# ProPrj_digisparkI2C_module_2026-01-09.net
KiCad netlist of a schematic drawn in EasyEDA Pro
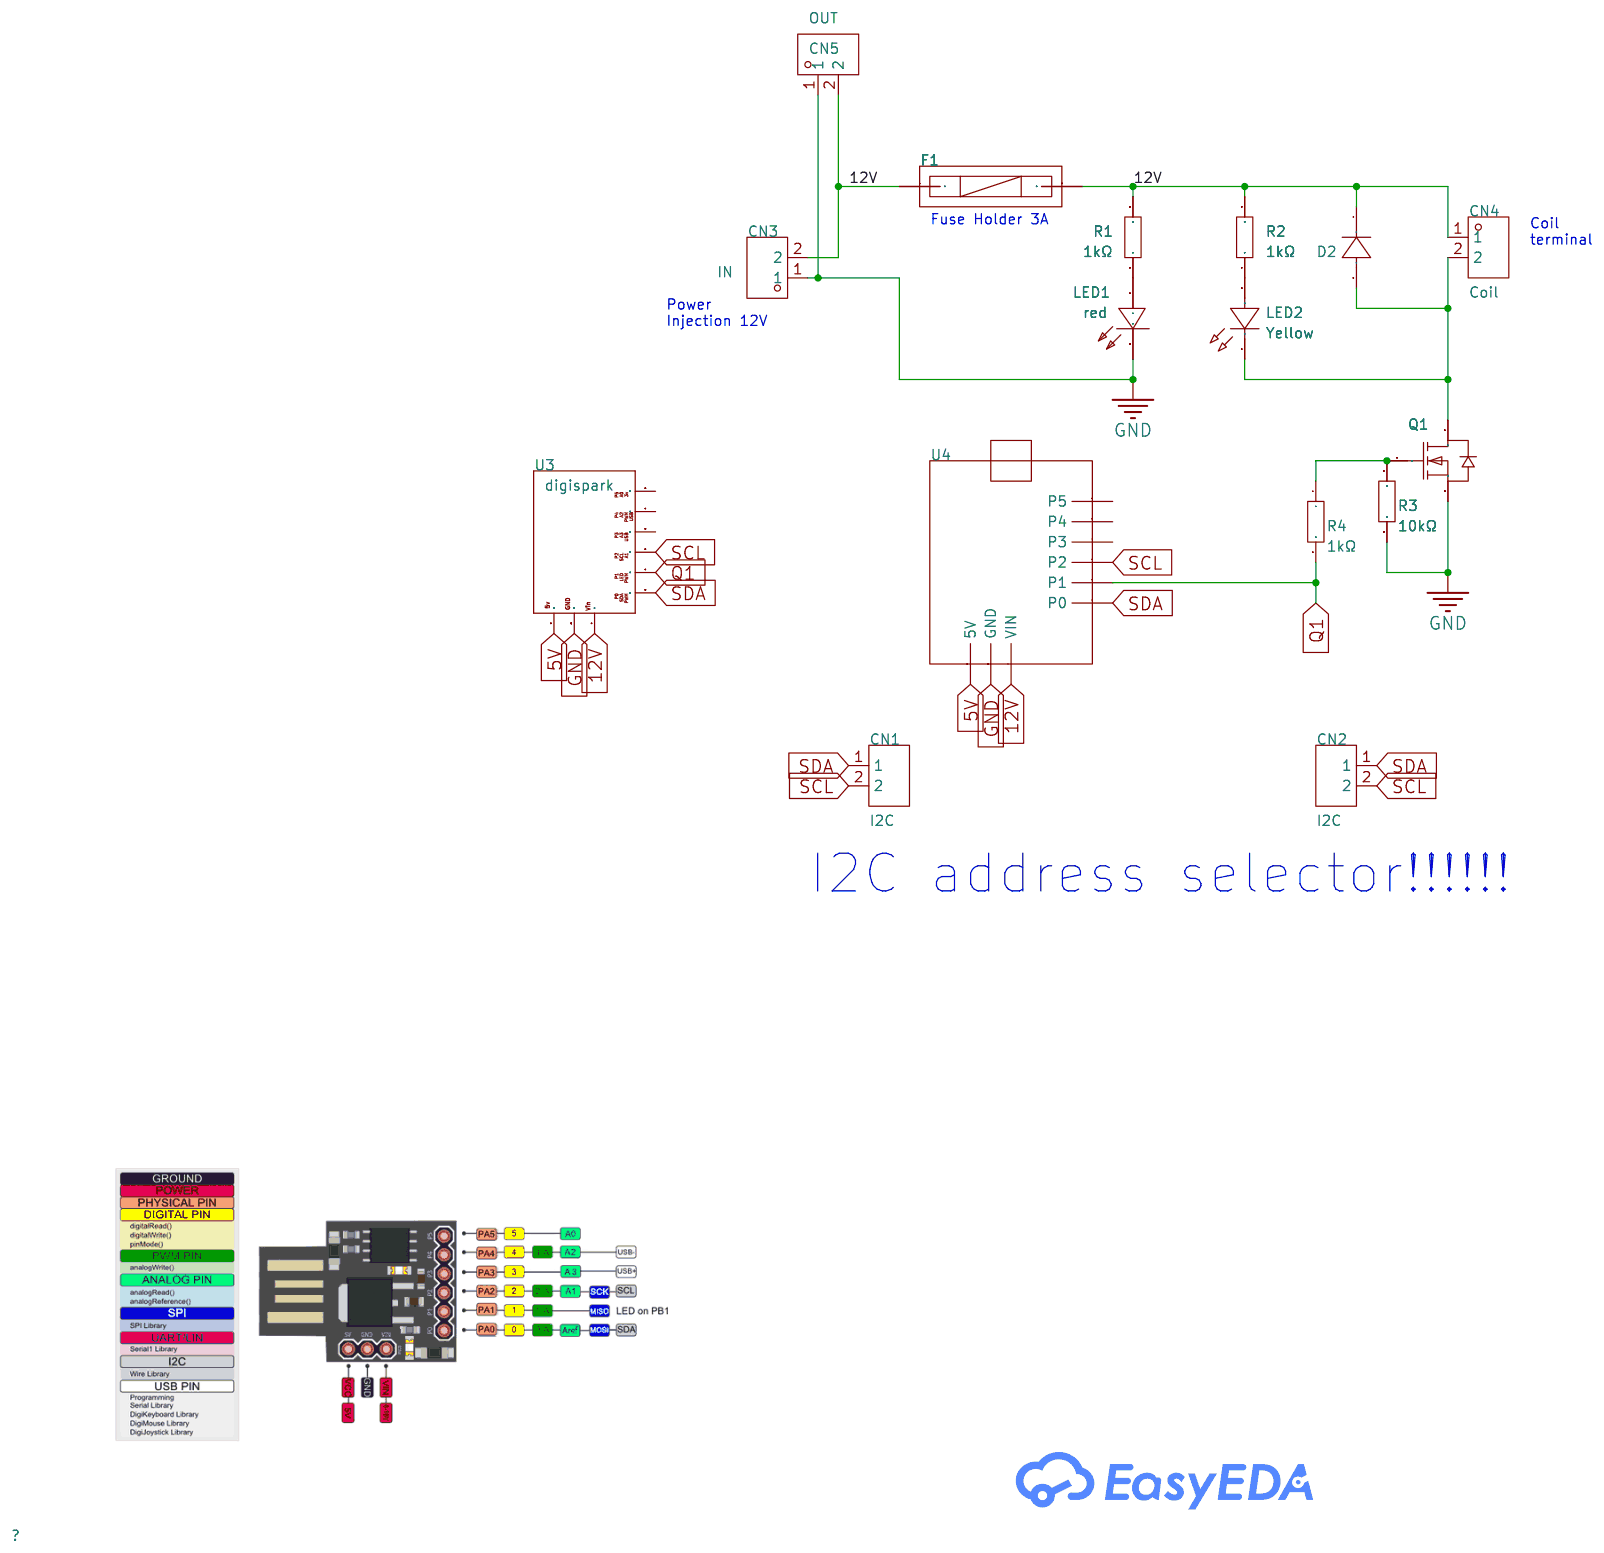
[diagram p0: schematic sheet]

(export (version "E")
  (design (tool "Eeschema 10.0.6"))
  (components
    (comp (ref "CN1")
      (value "I2C")
      (footprint "easyedapro:CONN-TH_2P-P2.50_XY-XH2.54-2A11-YT")
      (fields
        (field (name "Manufacturer Part") "XY-XH2.54-2A11-YT")
        (field (name "Manufacturer") "XYECONN(辛译)")
      )
      (libsource (lib "easyedapro") (part "XY-XH2.54-2A11-YT"))
    )
    (comp (ref "CN2")
      (value "I2C")
      (footprint "easyedapro:CONN-TH_2P-P2.50_XY-XH2.54-2A11-YT")
      (fields
        (field (name "Manufacturer Part") "XY-XH2.54-2A11-YT")
        (field (name "Manufacturer") "XYECONN(辛译)")
      )
      (libsource (lib "easyedapro") (part "XY-XH2.54-2A11-YT"))
    )
    (comp (ref "CN3")
      (value "IN")
      (footprint "easyedapro:CONN-TH_2P-P5.00_MX126-5.0-GN01-02P-CU-S-A")
      (fields
        (field (name "Manufacturer Part") "MX126-5.0-02P-GN01-Cu-S-A")
        (field (name "Manufacturer") "MAX(迈旭)")
      )
      (libsource (lib "easyedapro") (part "MX126-5.0-GN01-02P-CU-S-A"))
    )
    (comp (ref "CN4")
      (value "Coil")
      (footprint "easyedapro:CONN-TH_2P-P5.00_MX126-5.0-GN01-02P-CU-S-A")
      (fields
        (field (name "Manufacturer Part") "MX126-5.0-02P-GN01-Cu-S-A")
        (field (name "Manufacturer") "MAX(迈旭)")
      )
      (libsource (lib "easyedapro") (part "MX126-5.0-GN01-02P-CU-S-A"))
    )
    (comp (ref "CN5")
      (value "OUT")
      (footprint "easyedapro:CONN-TH_2P-P5.00_MX126-5.0-GN01-02P-CU-S-A")
      (fields
        (field (name "Manufacturer Part") "MX126-5.0-02P-GN01-Cu-S-A")
        (field (name "Manufacturer") "MAX(迈旭)")
      )
      (libsource (lib "easyedapro") (part "MX126-5.0-GN01-02P-CU-S-A"))
    )
    (comp (ref "D2")
      (value "~")
      (footprint "easyedapro:SMA_L4.4-W2.8-LS5.4-RD")
      (libsource (lib "easyedapro") (part "D_1N4007"))
    )
    (comp (ref "F1")
      (value "保险丝透明座")
      (footprint "easyedapro:FUSE-TH_L24.5-W9.8-P22.5")
      (description "Fuseholder Type:- Fuse Type:- Fuse Size:-")
      (fields (field (name "Manufacturer") "xcfuse(旭程)"))
      (libsource (lib "easyedapro") (part "Fuse transparent seat"))
    )
    (comp (ref "LED1")
      (value "red")
      (footprint "easyedapro:LED0805-R-RD-1")
      (description "Illumination Color:Red")
      (fields
        (field (name "Manufacturer Part") "17-21SURC/S530-A2/TR8")
        (field (name "Manufacturer") "EVERLIGHT(亿光)")
      )
      (libsource (lib "easyedapro") (part "17-21SURC/S530-A2/TR8"))
    )
    (comp (ref "LED2")
      (value "Yellow")
      (footprint "easyedapro:LED0805-RD_YELLOW")
      (fields (field (name "Manufacturer Part") "YLED0805Y") (field (name "Manufacturer") "YONGYUTAI(永裕泰)"))
      (libsource (lib "easyedapro") (part "YLED0805Y"))
    )
    (comp (ref "Q1")
      (value "IRLZ44NPBF-HXY")
      (footprint "easyedapro:TO-220-3_L9.9-W4.5-P2.54-L-1")
      (fields (field (name "Manufacturer") "HXY MOSFET(华轩阳电子)"))
      (libsource (lib "easyedapro") (part "IRLZ44NPBF-HXY"))
    )
    (comp (ref "R1") (value "1kΩ") (footprint "easyedapro:R1206") (libsource (lib "easyedapro") (part "Res")))
    (comp (ref "R2") (value "1kΩ") (footprint "easyedapro:R1206") (libsource (lib "easyedapro") (part "Res")))
    (comp (ref "R3")
      (value "10kΩ")
      (footprint "easyedapro:R1206")
      (libsource (lib "easyedapro") (part "Res"))
    )
    (comp (ref "R4") (value "1kΩ") (footprint "easyedapro:R1206") (libsource (lib "easyedapro") (part "Res")))
    (comp (ref "U3")
      (value "digispark")
      (footprint "easyedapro:DIGISPARK")
      (libsource (lib "easyedapro") (part "DIGISPARK_"))
    )
    (comp (ref "U4")
      (value "~")
      (footprint "easyedapro:ATtiny85 USB")
      (libsource (lib "easyedapro") (part "ATtiny85 USB"))
    )
  )
  (nets
    (net (code "1") (name "5V") (class "Default")
      (node (ref "U3") (pin "5V") (pinfunction "5V_5V") (pintype "input"))
      (node (ref "U4") (pin "9") (pinfunction "5V_9") (pintype "input"))
    )
    (net (code "2") (name "12V") (class "Default")
      (node (ref "CN3") (pin "2") (pinfunction "2_2") (pintype "unspecified"))
      (node (ref "CN4") (pin "1") (pinfunction "1_1") (pintype "unspecified"))
      (node (ref "CN5") (pin "2") (pinfunction "2_2") (pintype "unspecified"))
      (node (ref "D2") (pin "1") (pinfunction "K_1") (pintype "input"))
      (node (ref "F1") (pin "1") (pinfunction "1_1") (pintype "unspecified"))
      (node (ref "F1") (pin "2") (pinfunction "2_2") (pintype "unspecified"))
      (node (ref "R1") (pin "2") (pinfunction "2_2") (pintype "input"))
      (node (ref "R2") (pin "2") (pinfunction "2_2") (pintype "input"))
      (node (ref "U3") (pin "VIN") (pinfunction "VIN_VIN") (pintype "input"))
      (node (ref "U4") (pin "7") (pinfunction "VIN_7") (pintype "input"))
    )
    (net (code "3") (name "GND") (class "Default")
      (node (ref "CN3") (pin "1") (pinfunction "1_1") (pintype "unspecified"))
      (node (ref "CN5") (pin "1") (pinfunction "1_1") (pintype "unspecified"))
      (node (ref "LED1") (pin "2") (pinfunction "K_2") (pintype "unspecified"))
      (node (ref "Q1") (pin "3") (pinfunction "S_3") (pintype "unspecified"))
      (node (ref "R3") (pin "2") (pinfunction "2_2") (pintype "input"))
      (node (ref "U3") (pin "GND") (pinfunction "GND_GND") (pintype "input"))
      (node (ref "U4") (pin "8") (pinfunction "GND_8") (pintype "input"))
    )
    (net (code "4") (name "Net-(D2-A)") (class "Default")
      (node (ref "CN4") (pin "2") (pinfunction "2_2") (pintype "unspecified"))
      (node (ref "D2") (pin "2") (pinfunction "A_2") (pintype "input"))
      (node (ref "LED2") (pin "1") (pinfunction "K_1") (pintype "unspecified"))
      (node (ref "Q1") (pin "2") (pinfunction "D_2") (pintype "unspecified"))
    )
    (net (code "5") (name "Net-(LED1-A)") (class "Default")
      (node (ref "LED1") (pin "1") (pinfunction "A_1") (pintype "unspecified"))
      (node (ref "R1") (pin "1") (pinfunction "1_1") (pintype "input"))
    )
    (net (code "6") (name "Net-(LED2-A)") (class "Default")
      (node (ref "LED2") (pin "2") (pinfunction "A_2") (pintype "unspecified"))
      (node (ref "R2") (pin "1") (pinfunction "1_1") (pintype "input"))
    )
    (net (code "7") (name "Net-(Q1-G)") (class "Default")
      (node (ref "Q1") (pin "1") (pinfunction "G_1") (pintype "unspecified"))
      (node (ref "R3") (pin "1") (pinfunction "1_1") (pintype "input"))
      (node (ref "R4") (pin "1") (pinfunction "1_1") (pintype "input"))
    )
    (net (code "8") (name "Q1") (class "Default")
      (node (ref "R4") (pin "2") (pinfunction "2_2") (pintype "input"))
      (node (ref "U3") (pin "P1") (pinfunction "P1_P1") (pintype "input"))
      (node (ref "U4") (pin "2") (pinfunction "P1_2") (pintype "input"))
    )
    (net (code "9") (name "SCL") (class "Default")
      (node (ref "CN1") (pin "2") (pinfunction "2_2") (pintype "unspecified"))
      (node (ref "CN2") (pin "2") (pinfunction "2_2") (pintype "unspecified"))
      (node (ref "U3") (pin "P2") (pinfunction "P2_P2") (pintype "input"))
      (node (ref "U4") (pin "3") (pinfunction "P2_3") (pintype "input"))
    )
    (net (code "10") (name "SDA") (class "Default")
      (node (ref "CN1") (pin "1") (pinfunction "1_1") (pintype "unspecified"))
      (node (ref "CN2") (pin "1") (pinfunction "1_1") (pintype "unspecified"))
      (node (ref "U3") (pin "P0") (pinfunction "P0_P0") (pintype "input"))
      (node (ref "U4") (pin "1") (pinfunction "P0_1") (pintype "input"))
    )
    (net (code "11") (name "unconnected-(U3-PadP3)") (class "Default")
      (node (ref "U3") (pin "P3") (pinfunction "P3_P3") (pintype "input"))
    )
    (net (code "12") (name "unconnected-(U3-PadP4)") (class "Default")
      (node (ref "U3") (pin "P4") (pinfunction "P4_P4") (pintype "input"))
    )
    (net (code "13") (name "unconnected-(U3-PadP5)") (class "Default")
      (node (ref "U3") (pin "P5") (pinfunction "P5_P5") (pintype "input"))
    )
    (net (code "14") (name "unconnected-(U4-P3-Pad4)") (class "Default")
      (node (ref "U4") (pin "4") (pinfunction "P3_4") (pintype "input"))
    )
    (net (code "15") (name "unconnected-(U4-P4-Pad5)") (class "Default")
      (node (ref "U4") (pin "5") (pinfunction "P4_5") (pintype "input"))
    )
    (net (code "16") (name "unconnected-(U4-P5-Pad6)") (class "Default")
      (node (ref "U4") (pin "6") (pinfunction "P5_6") (pintype "input"))
    )
  )
)
